# usbToSerial.net
KiCad netlist of a schematic drawn in EAGLE
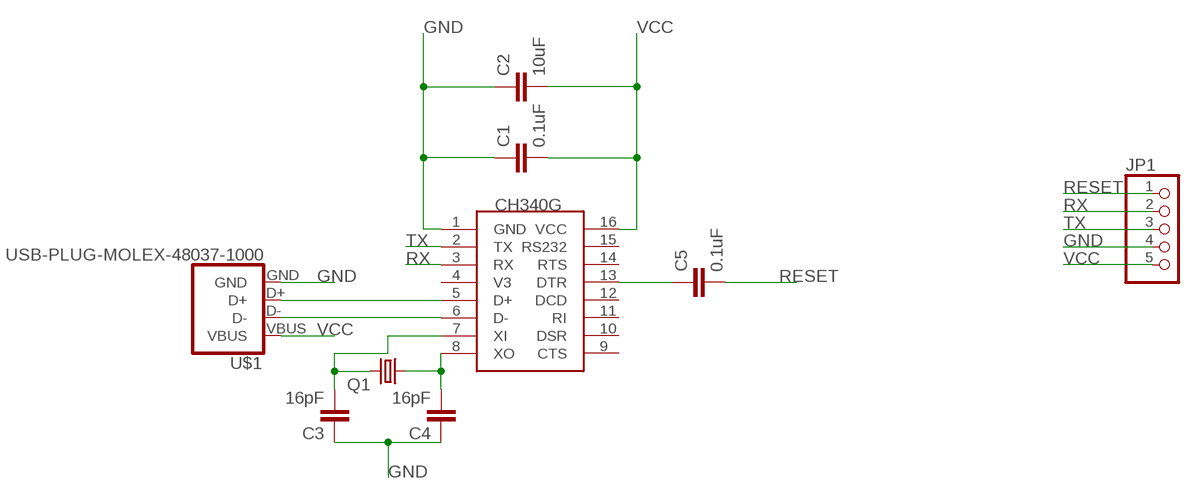
[diagram p0: schematic, sheet 1]

(export (version "E")
  (design (tool "Eeschema 10.0.6"))
  (components
    (comp (ref "C1")
      (value "0.1uF")
      (footprint "eagle-import:C0603")
      (libsource (lib "eagle-import") (part "C-EUC0603"))
    )
    (comp (ref "C2")
      (value "10uF")
      (footprint "eagle-import:C3216")
      (libsource (lib "eagle-import") (part "resistor_C-EUC3216"))
    )
    (comp (ref "C3")
      (value "16pF")
      (footprint "eagle-import:C0603")
      (libsource (lib "eagle-import") (part "C-EUC0603"))
    )
    (comp (ref "C4")
      (value "16pF")
      (footprint "eagle-import:C0603")
      (libsource (lib "eagle-import") (part "C-EUC0603"))
    )
    (comp (ref "C5")
      (value "0.1uF")
      (footprint "eagle-import:C0603")
      (libsource (lib "eagle-import") (part "C-EUC0603"))
    )
    (comp (ref "JP1")
      (value "PINHD-1X5/90")
      (footprint "eagle-import:1X05_90")
      (libsource (lib "eagle-import") (part "PINHD-1X5/90"))
    )
    (comp (ref "Q1")
      (value "CRYSTALSM49")
      (footprint "eagle-import:SM49")
      (libsource (lib "eagle-import") (part "CRYSTALSM49"))
    )
    (comp (ref "U$1")
      (value "USB-PLUG-MOLEX-48037-1000")
      (footprint "eagle-import:MOLEX-48037-1000")
      (libsource (lib "eagle-import") (part "USB-PLUG-MOLEX-48037-1000"))
    )
    (comp (ref "U$2")
      (value "CH340G")
      (footprint "eagle-import:SOIC16")
      (libsource (lib "eagle-import") (part "CH340G"))
    )
  )
  (nets
    (net (code "1") (name "/GND") (class "Default")
      (node (ref "C1") (pin "1") (pinfunction "1_1") (pintype "passive"))
      (node (ref "C2") (pin "1") (pinfunction "1_1") (pintype "passive"))
      (node (ref "C3") (pin "1") (pinfunction "1_1") (pintype "passive"))
      (node (ref "C4") (pin "1") (pinfunction "1_1") (pintype "passive"))
      (node (ref "JP1") (pin "4") (pinfunction "4_4") (pintype "passive"))
      (node (ref "U$1") (pin "GND") (pinfunction "GND_GND") (pintype "bidirectional"))
      (node (ref "U$2") (pin "1") (pinfunction "GND_1") (pintype "bidirectional"))
    )
    (net (code "2") (name "/RESET") (class "Default")
      (node (ref "C5") (pin "2") (pinfunction "2_2") (pintype "passive"))
      (node (ref "JP1") (pin "1") (pinfunction "1_1") (pintype "passive"))
    )
    (net (code "3") (name "/RX") (class "Default")
      (node (ref "JP1") (pin "2") (pinfunction "2_2") (pintype "passive"))
      (node (ref "U$2") (pin "3") (pinfunction "RX_3") (pintype "bidirectional"))
    )
    (net (code "4") (name "/TX") (class "Default")
      (node (ref "JP1") (pin "3") (pinfunction "3_3") (pintype "passive"))
      (node (ref "U$2") (pin "2") (pinfunction "TX_2") (pintype "bidirectional"))
    )
    (net (code "5") (name "/VCC") (class "Default")
      (node (ref "C1") (pin "2") (pinfunction "2_2") (pintype "passive"))
      (node (ref "C2") (pin "2") (pinfunction "2_2") (pintype "passive"))
      (node (ref "JP1") (pin "5") (pinfunction "5_5") (pintype "passive"))
      (node (ref "U$1") (pin "VBUS") (pinfunction "VBUS_VBUS") (pintype "bidirectional"))
      (node (ref "U$2") (pin "16") (pinfunction "VCC_16") (pintype "bidirectional"))
    )
    (net (code "6") (name "Net-(U$2-D+)") (class "Default")
      (node (ref "U$1") (pin "D+") (pinfunction "D+_D+") (pintype "bidirectional"))
      (node (ref "U$2") (pin "5") (pinfunction "D+_5") (pintype "bidirectional"))
    )
    (net (code "7") (name "Net-(U$2-D-)") (class "Default")
      (node (ref "U$1") (pin "D-") (pinfunction "D-_D-") (pintype "bidirectional"))
      (node (ref "U$2") (pin "6") (pinfunction "D-_6") (pintype "bidirectional"))
    )
    (net (code "8") (name "Net-(U$2-DTR)") (class "Default")
      (node (ref "C5") (pin "1") (pinfunction "1_1") (pintype "passive"))
      (node (ref "U$2") (pin "13") (pinfunction "DTR_13") (pintype "bidirectional"))
    )
    (net (code "9") (name "Net-(U$2-XI)") (class "Default")
      (node (ref "C3") (pin "2") (pinfunction "2_2") (pintype "passive"))
      (node (ref "Q1") (pin "2") (pinfunction "2_2") (pintype "passive"))
      (node (ref "U$2") (pin "7") (pinfunction "XI_7") (pintype "bidirectional"))
    )
    (net (code "10") (name "Net-(U$2-XO)") (class "Default")
      (node (ref "C4") (pin "2") (pinfunction "2_2") (pintype "passive"))
      (node (ref "Q1") (pin "1") (pinfunction "1_1") (pintype "passive"))
      (node (ref "U$2") (pin "8") (pinfunction "XO_8") (pintype "bidirectional"))
    )
    (net (code "11") (name "unconnected-(U$2-CTS-Pad9)") (class "Default")
      (node (ref "U$2") (pin "9") (pinfunction "CTS_9") (pintype "bidirectional"))
    )
    (net (code "12") (name "unconnected-(U$2-DCD-Pad12)") (class "Default")
      (node (ref "U$2") (pin "12") (pinfunction "DCD_12") (pintype "bidirectional"))
    )
    (net (code "13") (name "unconnected-(U$2-DSR-Pad10)") (class "Default")
      (node (ref "U$2") (pin "10") (pinfunction "DSR_10") (pintype "bidirectional"))
    )
    (net (code "14") (name "unconnected-(U$2-RI-Pad11)") (class "Default")
      (node (ref "U$2") (pin "11") (pinfunction "RI_11") (pintype "bidirectional"))
    )
    (net (code "15") (name "unconnected-(U$2-RS232-Pad15)") (class "Default")
      (node (ref "U$2") (pin "15") (pinfunction "RS232_15") (pintype "bidirectional"))
    )
    (net (code "16") (name "unconnected-(U$2-RTS-Pad14)") (class "Default")
      (node (ref "U$2") (pin "14") (pinfunction "RTS_14") (pintype "bidirectional"))
    )
    (net (code "17") (name "unconnected-(U$2-V3-Pad4)") (class "Default")
      (node (ref "U$2") (pin "4") (pinfunction "V3_4") (pintype "bidirectional"))
    )
  )
)
